# Encoder.net
KiCad netlist of a schematic drawn in EAGLE
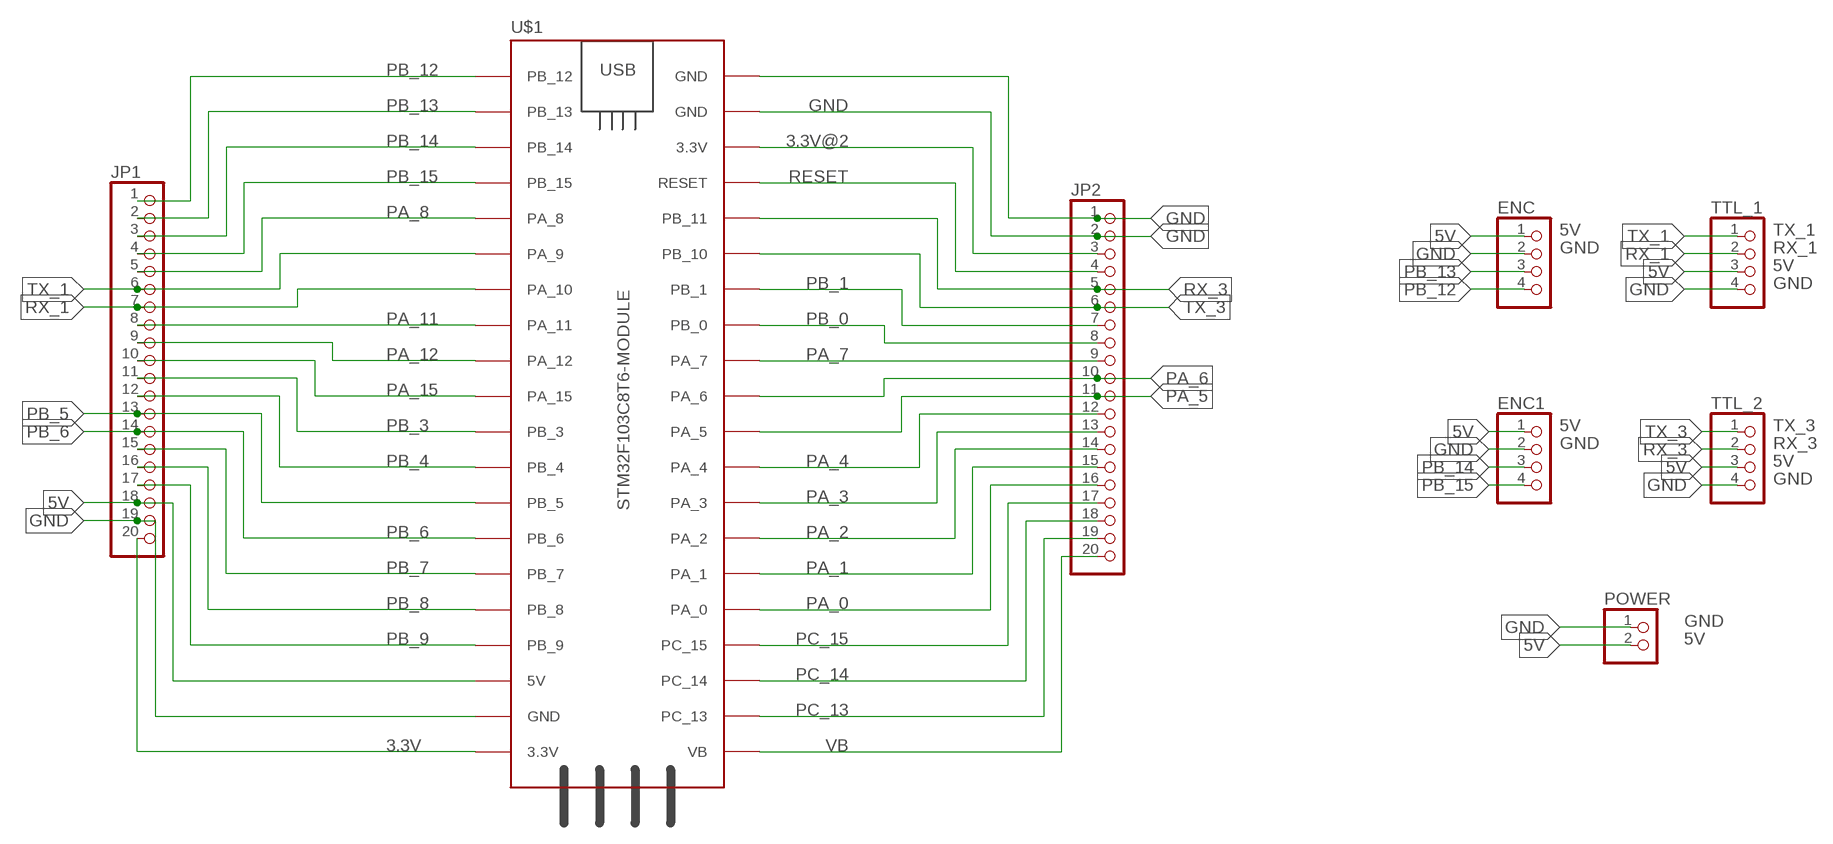
[diagram p0: schematic, sheet 1]

(export (version "E")
  (design (tool "Eeschema 10.0.6"))
  (components
    (comp (ref "ENC")
      (value "PINHD-4_DATA")
      (footprint "eagle-import:1X04_DATA")
      (libsource (lib "eagle-import") (part "PINHD-4_DATA"))
    )
    (comp (ref "ENC1")
      (value "PINHD-4_DATA")
      (footprint "eagle-import:1X04_DATA")
      (libsource (lib "eagle-import") (part "PINHD-4_DATA"))
    )
    (comp (ref "JP1")
      (value "PINHD-1X20")
      (footprint "eagle-import:1X20")
      (libsource (lib "eagle-import") (part "PINHD-1X20"))
    )
    (comp (ref "JP2")
      (value "PINHD-1X20")
      (footprint "eagle-import:1X20")
      (libsource (lib "eagle-import") (part "PINHD-1X20"))
    )
    (comp (ref "POWER")
      (value "PINHD-2_DATA")
      (footprint "eagle-import:1X02_DATA")
      (libsource (lib "eagle-import") (part "PINHD-2_DATA"))
    )
    (comp (ref "TTL_1")
      (value "PINHD-4_DATA")
      (footprint "eagle-import:1X04_DATA")
      (libsource (lib "eagle-import") (part "PINHD-4_DATA"))
    )
    (comp (ref "TTL_2")
      (value "PINHD-4_DATA")
      (footprint "eagle-import:1X04_DATA")
      (libsource (lib "eagle-import") (part "PINHD-4_DATA"))
    )
    (comp (ref "U$1")
      (value "STM32F103C8T6-MODULE")
      (footprint "eagle-import:STM32F103C8T6-MODULE")
      (libsource (lib "eagle-import") (part "STM32F103C8T6-MODULE"))
    )
  )
  (nets
    (net (code "1") (name "/3.3V") (class "Default")
      (node (ref "JP1") (pin "20") (pinfunction "20_20") (pintype "passive"))
      (node (ref "U$1") (pin "3.3V_1") (pinfunction "3.3V_3.3V_1") (pintype "bidirectional"))
    )
    (net (code "2") (name "/3.3V@2") (class "Default")
      (node (ref "JP2") (pin "3") (pinfunction "3_3") (pintype "passive"))
      (node (ref "U$1") (pin "3.3V_2") (pinfunction "3.3V_3.3V_2") (pintype "bidirectional"))
    )
    (net (code "3") (name "/PA_0") (class "Default")
      (node (ref "JP2") (pin "16") (pinfunction "16_16") (pintype "passive"))
      (node (ref "U$1") (pin "PA_0") (pinfunction "PA_0_PA_0") (pintype "bidirectional"))
    )
    (net (code "4") (name "/PA_1") (class "Default")
      (node (ref "JP2") (pin "15") (pinfunction "15_15") (pintype "passive"))
      (node (ref "U$1") (pin "PA_1") (pinfunction "PA_1_PA_1") (pintype "bidirectional"))
    )
    (net (code "5") (name "/PA_2") (class "Default")
      (node (ref "JP2") (pin "14") (pinfunction "14_14") (pintype "passive"))
      (node (ref "U$1") (pin "PA_2") (pinfunction "PA_2_PA_2") (pintype "bidirectional"))
    )
    (net (code "6") (name "/PA_3") (class "Default")
      (node (ref "JP2") (pin "13") (pinfunction "13_13") (pintype "passive"))
      (node (ref "U$1") (pin "PA_3") (pinfunction "PA_3_PA_3") (pintype "bidirectional"))
    )
    (net (code "7") (name "/PA_4") (class "Default")
      (node (ref "JP2") (pin "12") (pinfunction "12_12") (pintype "passive"))
      (node (ref "U$1") (pin "PA_4") (pinfunction "PA_4_PA_4") (pintype "bidirectional"))
    )
    (net (code "8") (name "/PA_7") (class "Default")
      (node (ref "JP2") (pin "9") (pinfunction "9_9") (pintype "passive"))
      (node (ref "U$1") (pin "PA_7") (pinfunction "PA_7_PA_7") (pintype "bidirectional"))
    )
    (net (code "9") (name "/PA_8") (class "Default")
      (node (ref "JP1") (pin "5") (pinfunction "5_5") (pintype "passive"))
      (node (ref "U$1") (pin "PA_8") (pinfunction "PA_8_PA_8") (pintype "bidirectional"))
    )
    (net (code "10") (name "/PA_11") (class "Default")
      (node (ref "JP1") (pin "8") (pinfunction "8_8") (pintype "passive"))
      (node (ref "U$1") (pin "PA_11") (pinfunction "PA_11_PA_11") (pintype "bidirectional"))
    )
    (net (code "11") (name "/PA_12") (class "Default")
      (node (ref "JP1") (pin "9") (pinfunction "9_9") (pintype "passive"))
      (node (ref "U$1") (pin "PA_12") (pinfunction "PA_12_PA_12") (pintype "bidirectional"))
    )
    (net (code "12") (name "/PA_15") (class "Default")
      (node (ref "JP1") (pin "10") (pinfunction "10_10") (pintype "passive"))
      (node (ref "U$1") (pin "PA_15") (pinfunction "PA_15_PA_15") (pintype "bidirectional"))
    )
    (net (code "13") (name "/PB_0") (class "Default")
      (node (ref "JP2") (pin "8") (pinfunction "8_8") (pintype "passive"))
      (node (ref "U$1") (pin "PB_0") (pinfunction "PB_0_PB_0") (pintype "bidirectional"))
    )
    (net (code "14") (name "/PB_1") (class "Default")
      (node (ref "JP2") (pin "7") (pinfunction "7_7") (pintype "passive"))
      (node (ref "U$1") (pin "PB_1") (pinfunction "PB_1_PB_1") (pintype "bidirectional"))
    )
    (net (code "15") (name "/PB_3") (class "Default")
      (node (ref "JP1") (pin "11") (pinfunction "11_11") (pintype "passive"))
      (node (ref "U$1") (pin "PB_3") (pinfunction "PB_3_PB_3") (pintype "bidirectional"))
    )
    (net (code "16") (name "/PB_4") (class "Default")
      (node (ref "JP1") (pin "12") (pinfunction "12_12") (pintype "passive"))
      (node (ref "U$1") (pin "PB_4") (pinfunction "PB_4_PB_4") (pintype "bidirectional"))
    )
    (net (code "17") (name "/PB_7") (class "Default")
      (node (ref "JP1") (pin "15") (pinfunction "15_15") (pintype "passive"))
      (node (ref "U$1") (pin "PB_7") (pinfunction "PB_7_PB_7") (pintype "bidirectional"))
    )
    (net (code "18") (name "/PB_8") (class "Default")
      (node (ref "JP1") (pin "16") (pinfunction "16_16") (pintype "passive"))
      (node (ref "U$1") (pin "PB_8") (pinfunction "PB_8_PB_8") (pintype "bidirectional"))
    )
    (net (code "19") (name "/PB_9") (class "Default")
      (node (ref "JP1") (pin "17") (pinfunction "17_17") (pintype "passive"))
      (node (ref "U$1") (pin "PB_9") (pinfunction "PB_9_PB_9") (pintype "bidirectional"))
    )
    (net (code "20") (name "/PC_13") (class "Default")
      (node (ref "JP2") (pin "19") (pinfunction "19_19") (pintype "passive"))
      (node (ref "U$1") (pin "PC_13") (pinfunction "PC_13_PC_13") (pintype "bidirectional"))
    )
    (net (code "21") (name "/PC_14") (class "Default")
      (node (ref "JP2") (pin "18") (pinfunction "18_18") (pintype "passive"))
      (node (ref "U$1") (pin "PC_14") (pinfunction "PC_14_PC_14") (pintype "bidirectional"))
    )
    (net (code "22") (name "/PC_15") (class "Default")
      (node (ref "JP2") (pin "17") (pinfunction "17_17") (pintype "passive"))
      (node (ref "U$1") (pin "PC_15") (pinfunction "PC_15_PC_15") (pintype "bidirectional"))
    )
    (net (code "23") (name "/RESET") (class "Default")
      (node (ref "JP2") (pin "4") (pinfunction "4_4") (pintype "passive"))
      (node (ref "U$1") (pin "RESET") (pinfunction "RESET_RESET") (pintype "bidirectional"))
    )
    (net (code "24") (name "/VB") (class "Default")
      (node (ref "JP2") (pin "20") (pinfunction "20_20") (pintype "passive"))
      (node (ref "U$1") (pin "VB") (pinfunction "VB_VB") (pintype "bidirectional"))
    )
    (net (code "25") (name "5V") (class "Default")
      (node (ref "ENC") (pin "1") (pinfunction "1_1") (pintype "passive"))
      (node (ref "ENC1") (pin "1") (pinfunction "1_1") (pintype "passive"))
      (node (ref "JP1") (pin "18") (pinfunction "18_18") (pintype "passive"))
      (node (ref "POWER") (pin "2") (pinfunction "2_2") (pintype "passive"))
      (node (ref "TTL_1") (pin "3") (pinfunction "3_3") (pintype "passive"))
      (node (ref "TTL_2") (pin "3") (pinfunction "3_3") (pintype "passive"))
      (node (ref "U$1") (pin "5V") (pinfunction "5V_5V") (pintype "bidirectional"))
    )
    (net (code "26") (name "GND") (class "Default")
      (node (ref "ENC") (pin "2") (pinfunction "2_2") (pintype "passive"))
      (node (ref "ENC1") (pin "2") (pinfunction "2_2") (pintype "passive"))
      (node (ref "JP1") (pin "19") (pinfunction "19_19") (pintype "passive"))
      (node (ref "JP2") (pin "1") (pinfunction "1_1") (pintype "passive"))
      (node (ref "JP2") (pin "2") (pinfunction "2_2") (pintype "passive"))
      (node (ref "POWER") (pin "1") (pinfunction "1_1") (pintype "passive"))
      (node (ref "TTL_1") (pin "4") (pinfunction "4_4") (pintype "passive"))
      (node (ref "TTL_2") (pin "4") (pinfunction "4_4") (pintype "passive"))
      (node (ref "U$1") (pin "GND_1") (pinfunction "GND_GND_1") (pintype "bidirectional"))
      (node (ref "U$1") (pin "GND_2") (pinfunction "GND_GND_2") (pintype "bidirectional"))
      (node (ref "U$1") (pin "GND_3") (pinfunction "GND_GND_3") (pintype "power_in"))
    )
    (net (code "27") (name "PA_5") (class "Default")
      (node (ref "JP2") (pin "11") (pinfunction "11_11") (pintype "passive"))
      (node (ref "U$1") (pin "PA_5") (pinfunction "PA_5_PA_5") (pintype "bidirectional"))
    )
    (net (code "28") (name "PA_6") (class "Default")
      (node (ref "JP2") (pin "10") (pinfunction "10_10") (pintype "passive"))
      (node (ref "U$1") (pin "PA_6") (pinfunction "PA_6_PA_6") (pintype "bidirectional"))
    )
    (net (code "29") (name "PB_5") (class "Default")
      (node (ref "JP1") (pin "13") (pinfunction "13_13") (pintype "passive"))
      (node (ref "U$1") (pin "PB_5") (pinfunction "PB_5_PB_5") (pintype "bidirectional"))
    )
    (net (code "30") (name "PB_6") (class "Default")
      (node (ref "JP1") (pin "14") (pinfunction "14_14") (pintype "passive"))
      (node (ref "U$1") (pin "PB_6") (pinfunction "PB_6_PB_6") (pintype "bidirectional"))
    )
    (net (code "31") (name "PB_12") (class "Default")
      (node (ref "ENC") (pin "4") (pinfunction "4_4") (pintype "passive"))
      (node (ref "JP1") (pin "1") (pinfunction "1_1") (pintype "passive"))
      (node (ref "U$1") (pin "PB_12") (pinfunction "PB_12_PB_12") (pintype "bidirectional"))
    )
    (net (code "32") (name "PB_13") (class "Default")
      (node (ref "ENC") (pin "3") (pinfunction "3_3") (pintype "passive"))
      (node (ref "JP1") (pin "2") (pinfunction "2_2") (pintype "passive"))
      (node (ref "U$1") (pin "PB_13") (pinfunction "PB_13_PB_13") (pintype "bidirectional"))
    )
    (net (code "33") (name "PB_14") (class "Default")
      (node (ref "ENC1") (pin "3") (pinfunction "3_3") (pintype "passive"))
      (node (ref "JP1") (pin "3") (pinfunction "3_3") (pintype "passive"))
      (node (ref "U$1") (pin "PB_14") (pinfunction "PB_14_PB_14") (pintype "bidirectional"))
    )
    (net (code "34") (name "PB_15") (class "Default")
      (node (ref "ENC1") (pin "4") (pinfunction "4_4") (pintype "passive"))
      (node (ref "JP1") (pin "4") (pinfunction "4_4") (pintype "passive"))
      (node (ref "U$1") (pin "PB_15") (pinfunction "PB_15_PB_15") (pintype "bidirectional"))
    )
    (net (code "35") (name "RX_1") (class "Default")
      (node (ref "JP1") (pin "7") (pinfunction "7_7") (pintype "passive"))
      (node (ref "TTL_1") (pin "2") (pinfunction "2_2") (pintype "passive"))
      (node (ref "U$1") (pin "PA_10") (pinfunction "PA_10_PA_10") (pintype "bidirectional"))
    )
    (net (code "36") (name "RX_3") (class "Default")
      (node (ref "JP2") (pin "5") (pinfunction "5_5") (pintype "passive"))
      (node (ref "TTL_2") (pin "2") (pinfunction "2_2") (pintype "passive"))
      (node (ref "U$1") (pin "PB_11") (pinfunction "PB_11_PB_11") (pintype "bidirectional"))
    )
    (net (code "37") (name "TX_1") (class "Default")
      (node (ref "JP1") (pin "6") (pinfunction "6_6") (pintype "passive"))
      (node (ref "TTL_1") (pin "1") (pinfunction "1_1") (pintype "passive"))
      (node (ref "U$1") (pin "PA_9") (pinfunction "PA_9_PA_9") (pintype "bidirectional"))
    )
    (net (code "38") (name "TX_3") (class "Default")
      (node (ref "JP2") (pin "6") (pinfunction "6_6") (pintype "passive"))
      (node (ref "TTL_2") (pin "1") (pinfunction "1_1") (pintype "passive"))
      (node (ref "U$1") (pin "PB_10") (pinfunction "PB_10_PB_10") (pintype "bidirectional"))
    )
  )
)
